# Brushed_DC.net
KiCad netlist of a schematic drawn in Altium Designer
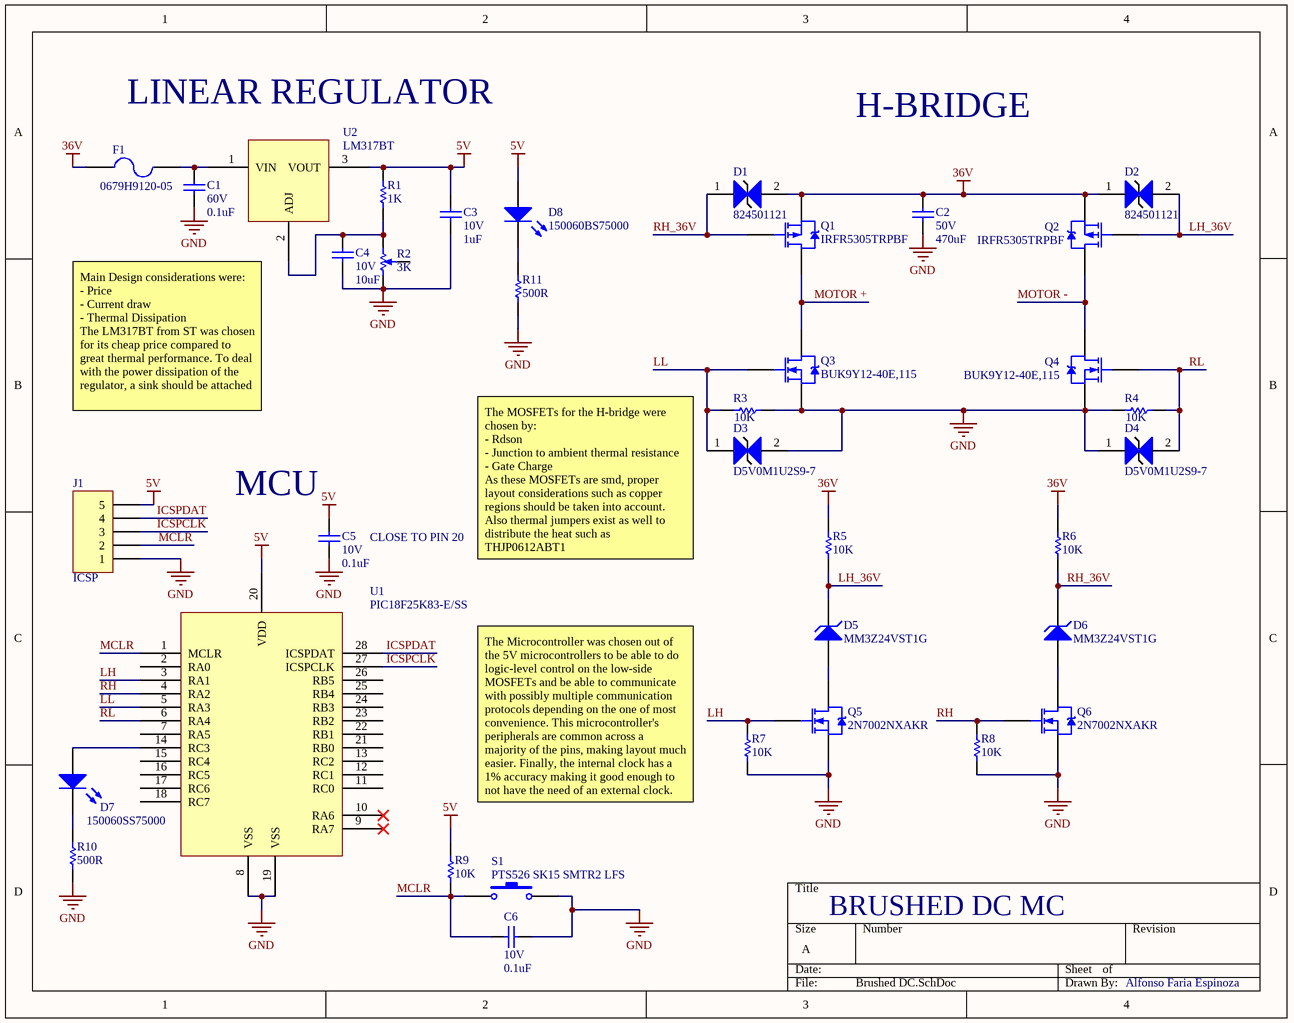
[diagram p0: Brushed DC.SchDoc]

(export (version "E")
  (design (tool "Eeschema 10.0.6"))
  (components
    (comp (ref "C1")
      (value "60V")
      (footprint "RAD-0.3")
      (description "Capacitor")
      (fields (field (name "ALTIUM_VALUE") "0.1uF") (field (name "PUBLISHER") "Altium Limited"))
      (libsource (lib "Miscellaneous Devices") (part "Cap"))
    )
    (comp (ref "C2")
      (value "50V")
      (footprint "RAD-0.3")
      (description "Capacitor")
      (fields (field (name "ALTIUM_VALUE") "470uF") (field (name "PUBLISHER") "Altium Limited"))
      (libsource (lib "Miscellaneous Devices") (part "Cap"))
    )
    (comp (ref "C3")
      (value "10V")
      (footprint "RAD-0.3")
      (description "Capacitor")
      (fields (field (name "ALTIUM_VALUE") "1uF") (field (name "PUBLISHER") "Altium Limited"))
      (libsource (lib "Miscellaneous Devices") (part "Cap"))
    )
    (comp (ref "C4")
      (value "10V")
      (footprint "RAD-0.3")
      (description "Capacitor")
      (fields (field (name "ALTIUM_VALUE") "10uF") (field (name "PUBLISHER") "Altium Limited"))
      (libsource (lib "Miscellaneous Devices") (part "Cap"))
    )
    (comp (ref "C5")
      (value "10V")
      (footprint "RAD-0.3")
      (description "Capacitor")
      (fields (field (name "ALTIUM_VALUE") "0.1uF") (field (name "PUBLISHER") "Altium Limited"))
      (libsource (lib "Miscellaneous Devices") (part "Cap"))
    )
    (comp (ref "C6")
      (value "10V")
      (footprint "RAD-0.3")
      (description "Capacitor")
      (fields (field (name "ALTIUM_VALUE") "0.1uF") (field (name "PUBLISHER") "Altium Limited"))
      (libsource (lib "Miscellaneous Devices") (part "Cap"))
    )
    (comp (ref "D1") (value "824501121") (libsource (lib "Brushed DC") (part "TVS")))
    (comp (ref "D2") (value "824501121") (libsource (lib "Brushed DC") (part "TVS")))
    (comp (ref "D3") (value "D5V0M1U2S9-7") (libsource (lib "Brushed DC") (part "TVS")))
    (comp (ref "D4") (value "D5V0M1U2S9-7") (libsource (lib "Brushed DC") (part "TVS")))
    (comp (ref "D5")
      (value "MM3Z24VST1G")
      (footprint "DIODE-0.7")
      (description "Zener Diode")
      (fields (field (name "PUBLISHER") "Altium Limited"))
      (libsource (lib "Miscellaneous Devices") (part "D Zener"))
    )
    (comp (ref "D6")
      (value "MM3Z24VST1G")
      (footprint "DIODE-0.7")
      (description "Zener Diode")
      (fields (field (name "PUBLISHER") "Altium Limited"))
      (libsource (lib "Miscellaneous Devices") (part "D Zener"))
    )
    (comp (ref "D7")
      (value "150060SS75000")
      (footprint "LED-0")
      (description "Typical INFRARED GaAs LED")
      (fields (field (name "PUBLISHER") "Altium Limited"))
      (libsource (lib "Miscellaneous Devices") (part "LED0"))
    )
    (comp (ref "D8")
      (value "150060BS75000")
      (footprint "LED-0")
      (description "Typical INFRARED GaAs LED")
      (fields (field (name "PUBLISHER") "Altium Limited"))
      (libsource (lib "Miscellaneous Devices") (part "LED0"))
    )
    (comp (ref "F1")
      (value "0679H9120-05")
      (footprint "PIN-W2/E2.8")
      (description "Fuse")
      (fields (field (name "PUBLISHER") "Altium Limited"))
      (libsource (lib "Miscellaneous Devices") (part "Fuse 2"))
    )
    (comp (ref "J1")
      (value "ICSP")
      (footprint "HDR1X5")
      (description "Header, 5-Pin")
      (fields (field (name "PUBLISHER") "Altium Limited"))
      (libsource (lib "Miscellaneous Connectors") (part "Header 5"))
    )
    (comp (ref "Q1")
      (value "IRFR5305TRPBF")
      (footprint "TO-220AB")
      (description "P-Channel Power MOSFET")
      (fields (field (name "PUBLISHER") "Altium Limited"))
      (libsource (lib "Miscellaneous Devices") (part "PMOS-2"))
    )
    (comp (ref "Q2")
      (value "IRFR5305TRPBF")
      (footprint "TO-220AB")
      (description "P-Channel Power MOSFET")
      (fields (field (name "PUBLISHER") "Altium Limited"))
      (libsource (lib "Miscellaneous Devices") (part "PMOS-2"))
    )
    (comp (ref "Q3")
      (value "BUK9Y12-40E,115")
      (footprint "TO-220AB")
      (description "N-Channel Power MOSFET")
      (fields (field (name "PUBLISHER") "Altium Limited"))
      (libsource (lib "Miscellaneous Devices") (part "NMOS-2"))
    )
    (comp (ref "Q4")
      (value "BUK9Y12-40E,115")
      (footprint "TO-220AB")
      (description "N-Channel Power MOSFET")
      (fields (field (name "PUBLISHER") "Altium Limited"))
      (libsource (lib "Miscellaneous Devices") (part "NMOS-2"))
    )
    (comp (ref "Q5")
      (value "2N7002NXAKR")
      (footprint "TO-220AB")
      (description "N-Channel Power MOSFET")
      (fields (field (name "PUBLISHER") "Altium Limited"))
      (libsource (lib "Miscellaneous Devices") (part "NMOS-2"))
    )
    (comp (ref "Q6")
      (value "2N7002NXAKR")
      (footprint "TO-220AB")
      (description "N-Channel Power MOSFET")
      (fields (field (name "PUBLISHER") "Altium Limited"))
      (libsource (lib "Miscellaneous Devices") (part "NMOS-2"))
    )
    (comp (ref "R1")
      (value "1K")
      (footprint "AXIAL-0.3")
      (description "Resistor")
      (fields (field (name "Comment") "Res1") (field (name "PUBLISHER") "Altium Limited"))
      (libsource (lib "Miscellaneous Devices") (part "Res1"))
    )
    (comp (ref "R2")
      (value "3K")
      (footprint "POT4MM-2")
      (description "Square Trimming Potentiometer")
      (fields (field (name "PUBLISHER") "Altium Limited"))
      (libsource (lib "Miscellaneous Devices") (part "RPot SM"))
    )
    (comp (ref "R3")
      (value "10K")
      (footprint "AXIAL-0.3")
      (description "Resistor")
      (fields (field (name "Comment") "Res1") (field (name "PUBLISHER") "Altium Limited"))
      (libsource (lib "Miscellaneous Devices") (part "Res1"))
    )
    (comp (ref "R4")
      (value "10K")
      (footprint "AXIAL-0.3")
      (description "Resistor")
      (fields (field (name "Comment") "Res1") (field (name "PUBLISHER") "Altium Limited"))
      (libsource (lib "Miscellaneous Devices") (part "Res1"))
    )
    (comp (ref "R5")
      (value "10K")
      (footprint "AXIAL-0.3")
      (description "Resistor")
      (fields (field (name "Comment") "Res1") (field (name "PUBLISHER") "Altium Limited"))
      (libsource (lib "Miscellaneous Devices") (part "Res1"))
    )
    (comp (ref "R6")
      (value "10K")
      (footprint "AXIAL-0.3")
      (description "Resistor")
      (fields (field (name "Comment") "Res1") (field (name "PUBLISHER") "Altium Limited"))
      (libsource (lib "Miscellaneous Devices") (part "Res1"))
    )
    (comp (ref "R7")
      (value "10K")
      (footprint "AXIAL-0.3")
      (description "Resistor")
      (fields (field (name "Comment") "Res1") (field (name "PUBLISHER") "Altium Limited"))
      (libsource (lib "Miscellaneous Devices") (part "Res1"))
    )
    (comp (ref "R8")
      (value "10K")
      (footprint "AXIAL-0.3")
      (description "Resistor")
      (fields (field (name "Comment") "Res1") (field (name "PUBLISHER") "Altium Limited"))
      (libsource (lib "Miscellaneous Devices") (part "Res1"))
    )
    (comp (ref "R9")
      (value "10K")
      (footprint "AXIAL-0.3")
      (description "Resistor")
      (fields (field (name "Comment") "Res1") (field (name "PUBLISHER") "Altium Limited"))
      (libsource (lib "Miscellaneous Devices") (part "Res1"))
    )
    (comp (ref "R10")
      (value "500R")
      (footprint "AXIAL-0.3")
      (description "Resistor")
      (fields (field (name "Comment") "Res1") (field (name "PUBLISHER") "Altium Limited"))
      (libsource (lib "Miscellaneous Devices") (part "Res1"))
    )
    (comp (ref "R11")
      (value "500R")
      (footprint "AXIAL-0.3")
      (description "Resistor")
      (fields (field (name "Comment") "Res1") (field (name "PUBLISHER") "Altium Limited"))
      (libsource (lib "Miscellaneous Devices") (part "Res1"))
    )
    (comp (ref "S1")
      (value "PTS526 SK15 SMTR2 LFS")
      (footprint "SPST-2")
      (description "Switch")
      (fields (field (name "PUBLISHER") "Altium Limited"))
      (libsource (lib "Miscellaneous Devices") (part "SW-PB"))
    )
    (comp (ref "U1") (value "PIC18F25K83-E/SS") (libsource (lib "Brushed DC") (part "PIC18F25K83-E/SS")))
    (comp (ref "U2")
      (value "LM317BT")
      (description "Linear Voltage Regulator IC 1 Output 1.5A TO-220")
      (libsource (lib "Brushed DC") (part "LM317BT"))
    )
  )
  (nets
    (net (code "1") (name "/ICSPCLK") (class "Default")
      (node (ref "J1") (pin "3") (pinfunction "3_3") (pintype "passive"))
      (node (ref "U1") (pin "27") (pinfunction "ICSPCLK_27") (pintype "passive"))
    )
    (net (code "2") (name "/ICSPDAT") (class "Default")
      (node (ref "J1") (pin "4") (pinfunction "4_4") (pintype "passive"))
      (node (ref "U1") (pin "28") (pinfunction "ICSPDAT_28") (pintype "passive"))
    )
    (net (code "3") (name "/LH") (class "Default")
      (node (ref "Q5") (pin "1") (pinfunction "G_1") (pintype "passive"))
      (node (ref "R7") (pin "2") (pinfunction "2_2") (pintype "passive"))
      (node (ref "U1") (pin "3") (pinfunction "RA1_3") (pintype "passive"))
    )
    (net (code "4") (name "/LH_36V") (class "Default")
      (node (ref "D2") (pin "2") (pinfunction "2_2") (pintype "passive"))
      (node (ref "D5") (pin "2") (pinfunction "K_2") (pintype "passive"))
      (node (ref "Q2") (pin "1") (pinfunction "G_1") (pintype "passive"))
      (node (ref "R5") (pin "1") (pinfunction "1_1") (pintype "passive"))
    )
    (net (code "5") (name "/LL") (class "Default")
      (node (ref "D3") (pin "1") (pinfunction "1_1") (pintype "passive"))
      (node (ref "Q3") (pin "1") (pinfunction "G_1") (pintype "passive"))
      (node (ref "R3") (pin "1") (pinfunction "1_1") (pintype "passive"))
      (node (ref "U1") (pin "5") (pinfunction "RA3_5") (pintype "passive"))
    )
    (net (code "6") (name "/MCLR") (class "Default")
      (node (ref "C6") (pin "2") (pinfunction "2_2") (pintype "passive"))
      (node (ref "J1") (pin "2") (pinfunction "2_2") (pintype "passive"))
      (node (ref "R9") (pin "1") (pinfunction "1_1") (pintype "passive"))
      (node (ref "S1") (pin "1") (pinfunction "1_1") (pintype "passive"))
      (node (ref "U1") (pin "1") (pinfunction "MCLR_1") (pintype "passive"))
    )
    (net (code "7") (name "/MOTOR +") (class "Default")
      (node (ref "Q1") (pin "2") (pinfunction "D_2") (pintype "passive"))
      (node (ref "Q3") (pin "2") (pinfunction "D_2") (pintype "passive"))
    )
    (net (code "8") (name "/MOTOR -") (class "Default")
      (node (ref "Q2") (pin "2") (pinfunction "D_2") (pintype "passive"))
      (node (ref "Q4") (pin "2") (pinfunction "D_2") (pintype "passive"))
    )
    (net (code "9") (name "/RH") (class "Default")
      (node (ref "Q6") (pin "1") (pinfunction "G_1") (pintype "passive"))
      (node (ref "R8") (pin "2") (pinfunction "2_2") (pintype "passive"))
      (node (ref "U1") (pin "4") (pinfunction "RA2_4") (pintype "passive"))
    )
    (net (code "10") (name "/RH_36V") (class "Default")
      (node (ref "D1") (pin "1") (pinfunction "1_1") (pintype "passive"))
      (node (ref "D6") (pin "2") (pinfunction "K_2") (pintype "passive"))
      (node (ref "Q1") (pin "1") (pinfunction "G_1") (pintype "passive"))
      (node (ref "R6") (pin "1") (pinfunction "1_1") (pintype "passive"))
    )
    (net (code "11") (name "/RL") (class "Default")
      (node (ref "D4") (pin "2") (pinfunction "2_2") (pintype "passive"))
      (node (ref "Q4") (pin "1") (pinfunction "G_1") (pintype "passive"))
      (node (ref "R4") (pin "2") (pinfunction "2_2") (pintype "passive"))
      (node (ref "U1") (pin "6") (pinfunction "RA4_6") (pintype "passive"))
    )
    (net (code "12") (name "5V") (class "Default")
      (node (ref "C3") (pin "2") (pinfunction "2_2") (pintype "passive"))
      (node (ref "C5") (pin "2") (pinfunction "2_2") (pintype "passive"))
      (node (ref "D8") (pin "1") (pinfunction "A_1") (pintype "passive"))
      (node (ref "J1") (pin "5") (pinfunction "5_5") (pintype "passive"))
      (node (ref "R1") (pin "2") (pinfunction "2_2") (pintype "passive"))
      (node (ref "R9") (pin "2") (pinfunction "2_2") (pintype "passive"))
      (node (ref "U1") (pin "20") (pinfunction "VDD_20") (pintype "power_in"))
      (node (ref "U2") (pin "3") (pinfunction "VOUT_3") (pintype "power_in"))
    )
    (net (code "13") (name "36V") (class "Default")
      (node (ref "C2") (pin "2") (pinfunction "2_2") (pintype "passive"))
      (node (ref "D1") (pin "2") (pinfunction "2_2") (pintype "passive"))
      (node (ref "D2") (pin "1") (pinfunction "1_1") (pintype "passive"))
      (node (ref "F1") (pin "1") (pinfunction "1_1") (pintype "passive"))
      (node (ref "Q1") (pin "3") (pinfunction "S_3") (pintype "passive"))
      (node (ref "Q2") (pin "3") (pinfunction "S_3") (pintype "passive"))
      (node (ref "R5") (pin "2") (pinfunction "2_2") (pintype "passive"))
      (node (ref "R6") (pin "2") (pinfunction "2_2") (pintype "passive"))
    )
    (net (code "14") (name "GND") (class "Default")
      (node (ref "C1") (pin "1") (pinfunction "1_1") (pintype "passive"))
      (node (ref "C2") (pin "1") (pinfunction "1_1") (pintype "passive"))
      (node (ref "C3") (pin "1") (pinfunction "1_1") (pintype "passive"))
      (node (ref "C4") (pin "1") (pinfunction "1_1") (pintype "passive"))
      (node (ref "C5") (pin "1") (pinfunction "1_1") (pintype "passive"))
      (node (ref "C6") (pin "1") (pinfunction "1_1") (pintype "passive"))
      (node (ref "D3") (pin "2") (pinfunction "2_2") (pintype "passive"))
      (node (ref "D4") (pin "1") (pinfunction "1_1") (pintype "passive"))
      (node (ref "J1") (pin "1") (pinfunction "1_1") (pintype "passive"))
      (node (ref "Q3") (pin "3") (pinfunction "S_3") (pintype "passive"))
      (node (ref "Q4") (pin "3") (pinfunction "S_3") (pintype "passive"))
      (node (ref "Q5") (pin "3") (pinfunction "S_3") (pintype "passive"))
      (node (ref "Q6") (pin "3") (pinfunction "S_3") (pintype "passive"))
      (node (ref "R10") (pin "1") (pinfunction "1_1") (pintype "passive"))
      (node (ref "R11") (pin "1") (pinfunction "1_1") (pintype "passive"))
      (node (ref "R2") (pin "CCW") (pinfunction "-_CCW") (pintype "passive"))
      (node (ref "R3") (pin "2") (pinfunction "2_2") (pintype "passive"))
      (node (ref "R4") (pin "1") (pinfunction "1_1") (pintype "passive"))
      (node (ref "R7") (pin "1") (pinfunction "1_1") (pintype "passive"))
      (node (ref "R8") (pin "1") (pinfunction "1_1") (pintype "passive"))
      (node (ref "S1") (pin "2") (pinfunction "2_2") (pintype "passive"))
      (node (ref "U1") (pin "19") (pinfunction "VSS_19") (pintype "power_in"))
      (node (ref "U1") (pin "8") (pinfunction "VSS_8") (pintype "power_in"))
    )
    (net (code "15") (name "Net-(D5-A)") (class "Default")
      (node (ref "D5") (pin "1") (pinfunction "A_1") (pintype "passive"))
      (node (ref "Q5") (pin "2") (pinfunction "D_2") (pintype "passive"))
    )
    (net (code "16") (name "Net-(D6-A)") (class "Default")
      (node (ref "D6") (pin "1") (pinfunction "A_1") (pintype "passive"))
      (node (ref "Q6") (pin "2") (pinfunction "D_2") (pintype "passive"))
    )
    (net (code "17") (name "Net-(D7-A)") (class "Default")
      (node (ref "D7") (pin "1") (pinfunction "A_1") (pintype "passive"))
      (node (ref "U1") (pin "14") (pinfunction "RC3_14") (pintype "passive"))
    )
    (net (code "18") (name "Net-(D7-K)") (class "Default")
      (node (ref "D7") (pin "2") (pinfunction "K_2") (pintype "passive"))
      (node (ref "R10") (pin "2") (pinfunction "2_2") (pintype "passive"))
    )
    (net (code "19") (name "Net-(D8-K)") (class "Default")
      (node (ref "D8") (pin "2") (pinfunction "K_2") (pintype "passive"))
      (node (ref "R11") (pin "2") (pinfunction "2_2") (pintype "passive"))
    )
    (net (code "20") (name "Net-(R2-+)") (class "Default")
      (node (ref "C4") (pin "2") (pinfunction "2_2") (pintype "passive"))
      (node (ref "R1") (pin "1") (pinfunction "1_1") (pintype "passive"))
      (node (ref "R2") (pin "CW") (pinfunction "+_CW") (pintype "passive"))
      (node (ref "U2") (pin "2") (pinfunction "ADJ_2") (pintype "passive"))
    )
    (net (code "21") (name "Net-(U2-VIN)") (class "Default")
      (node (ref "C1") (pin "2") (pinfunction "2_2") (pintype "passive"))
      (node (ref "F1") (pin "2") (pinfunction "2_2") (pintype "passive"))
      (node (ref "U2") (pin "1") (pinfunction "VIN_1") (pintype "power_in"))
    )
    (net (code "22") (name "unconnected-(R2-PadW)") (class "Default")
      (node (ref "R2") (pin "W") (pinfunction "W_W") (pintype "passive"))
    )
    (net (code "23") (name "unconnected-(U1-RA0-Pad2)") (class "Default")
      (node (ref "U1") (pin "2") (pinfunction "RA0_2") (pintype "passive"))
    )
    (net (code "24") (name "unconnected-(U1-RA5-Pad7)") (class "Default")
      (node (ref "U1") (pin "7") (pinfunction "RA5_7") (pintype "passive"))
    )
    (net (code "25") (name "unconnected-(U1-RA6-Pad10)") (class "Default")
      (node (ref "U1") (pin "10") (pinfunction "RA6_10") (pintype "passive+no_connect"))
    )
    (net (code "26") (name "unconnected-(U1-RA7-Pad9)") (class "Default")
      (node (ref "U1") (pin "9") (pinfunction "RA7_9") (pintype "passive+no_connect"))
    )
    (net (code "27") (name "unconnected-(U1-RB0-Pad21)") (class "Default")
      (node (ref "U1") (pin "21") (pinfunction "RB0_21") (pintype "passive"))
    )
    (net (code "28") (name "unconnected-(U1-RB1-Pad22)") (class "Default")
      (node (ref "U1") (pin "22") (pinfunction "RB1_22") (pintype "passive"))
    )
    (net (code "29") (name "unconnected-(U1-RB2-Pad23)") (class "Default")
      (node (ref "U1") (pin "23") (pinfunction "RB2_23") (pintype "passive"))
    )
    (net (code "30") (name "unconnected-(U1-RB3-Pad24)") (class "Default")
      (node (ref "U1") (pin "24") (pinfunction "RB3_24") (pintype "passive"))
    )
    (net (code "31") (name "unconnected-(U1-RB4-Pad25)") (class "Default")
      (node (ref "U1") (pin "25") (pinfunction "RB4_25") (pintype "passive"))
    )
    (net (code "32") (name "unconnected-(U1-RB5-Pad26)") (class "Default")
      (node (ref "U1") (pin "26") (pinfunction "RB5_26") (pintype "passive"))
    )
    (net (code "33") (name "unconnected-(U1-RC0-Pad11)") (class "Default")
      (node (ref "U1") (pin "11") (pinfunction "RC0_11") (pintype "passive"))
    )
    (net (code "34") (name "unconnected-(U1-RC1-Pad12)") (class "Default")
      (node (ref "U1") (pin "12") (pinfunction "RC1_12") (pintype "passive"))
    )
    (net (code "35") (name "unconnected-(U1-RC2-Pad13)") (class "Default")
      (node (ref "U1") (pin "13") (pinfunction "RC2_13") (pintype "passive"))
    )
    (net (code "36") (name "unconnected-(U1-RC4-Pad15)") (class "Default")
      (node (ref "U1") (pin "15") (pinfunction "RC4_15") (pintype "passive"))
    )
    (net (code "37") (name "unconnected-(U1-RC5-Pad16)") (class "Default")
      (node (ref "U1") (pin "16") (pinfunction "RC5_16") (pintype "passive"))
    )
    (net (code "38") (name "unconnected-(U1-RC6-Pad17)") (class "Default")
      (node (ref "U1") (pin "17") (pinfunction "RC6_17") (pintype "passive"))
    )
    (net (code "39") (name "unconnected-(U1-RC7-Pad18)") (class "Default")
      (node (ref "U1") (pin "18") (pinfunction "RC7_18") (pintype "passive"))
    )
  )
)
